# DM2097_Power_Supply.net
KiCad netlist of a schematic drawn in Altium Designer
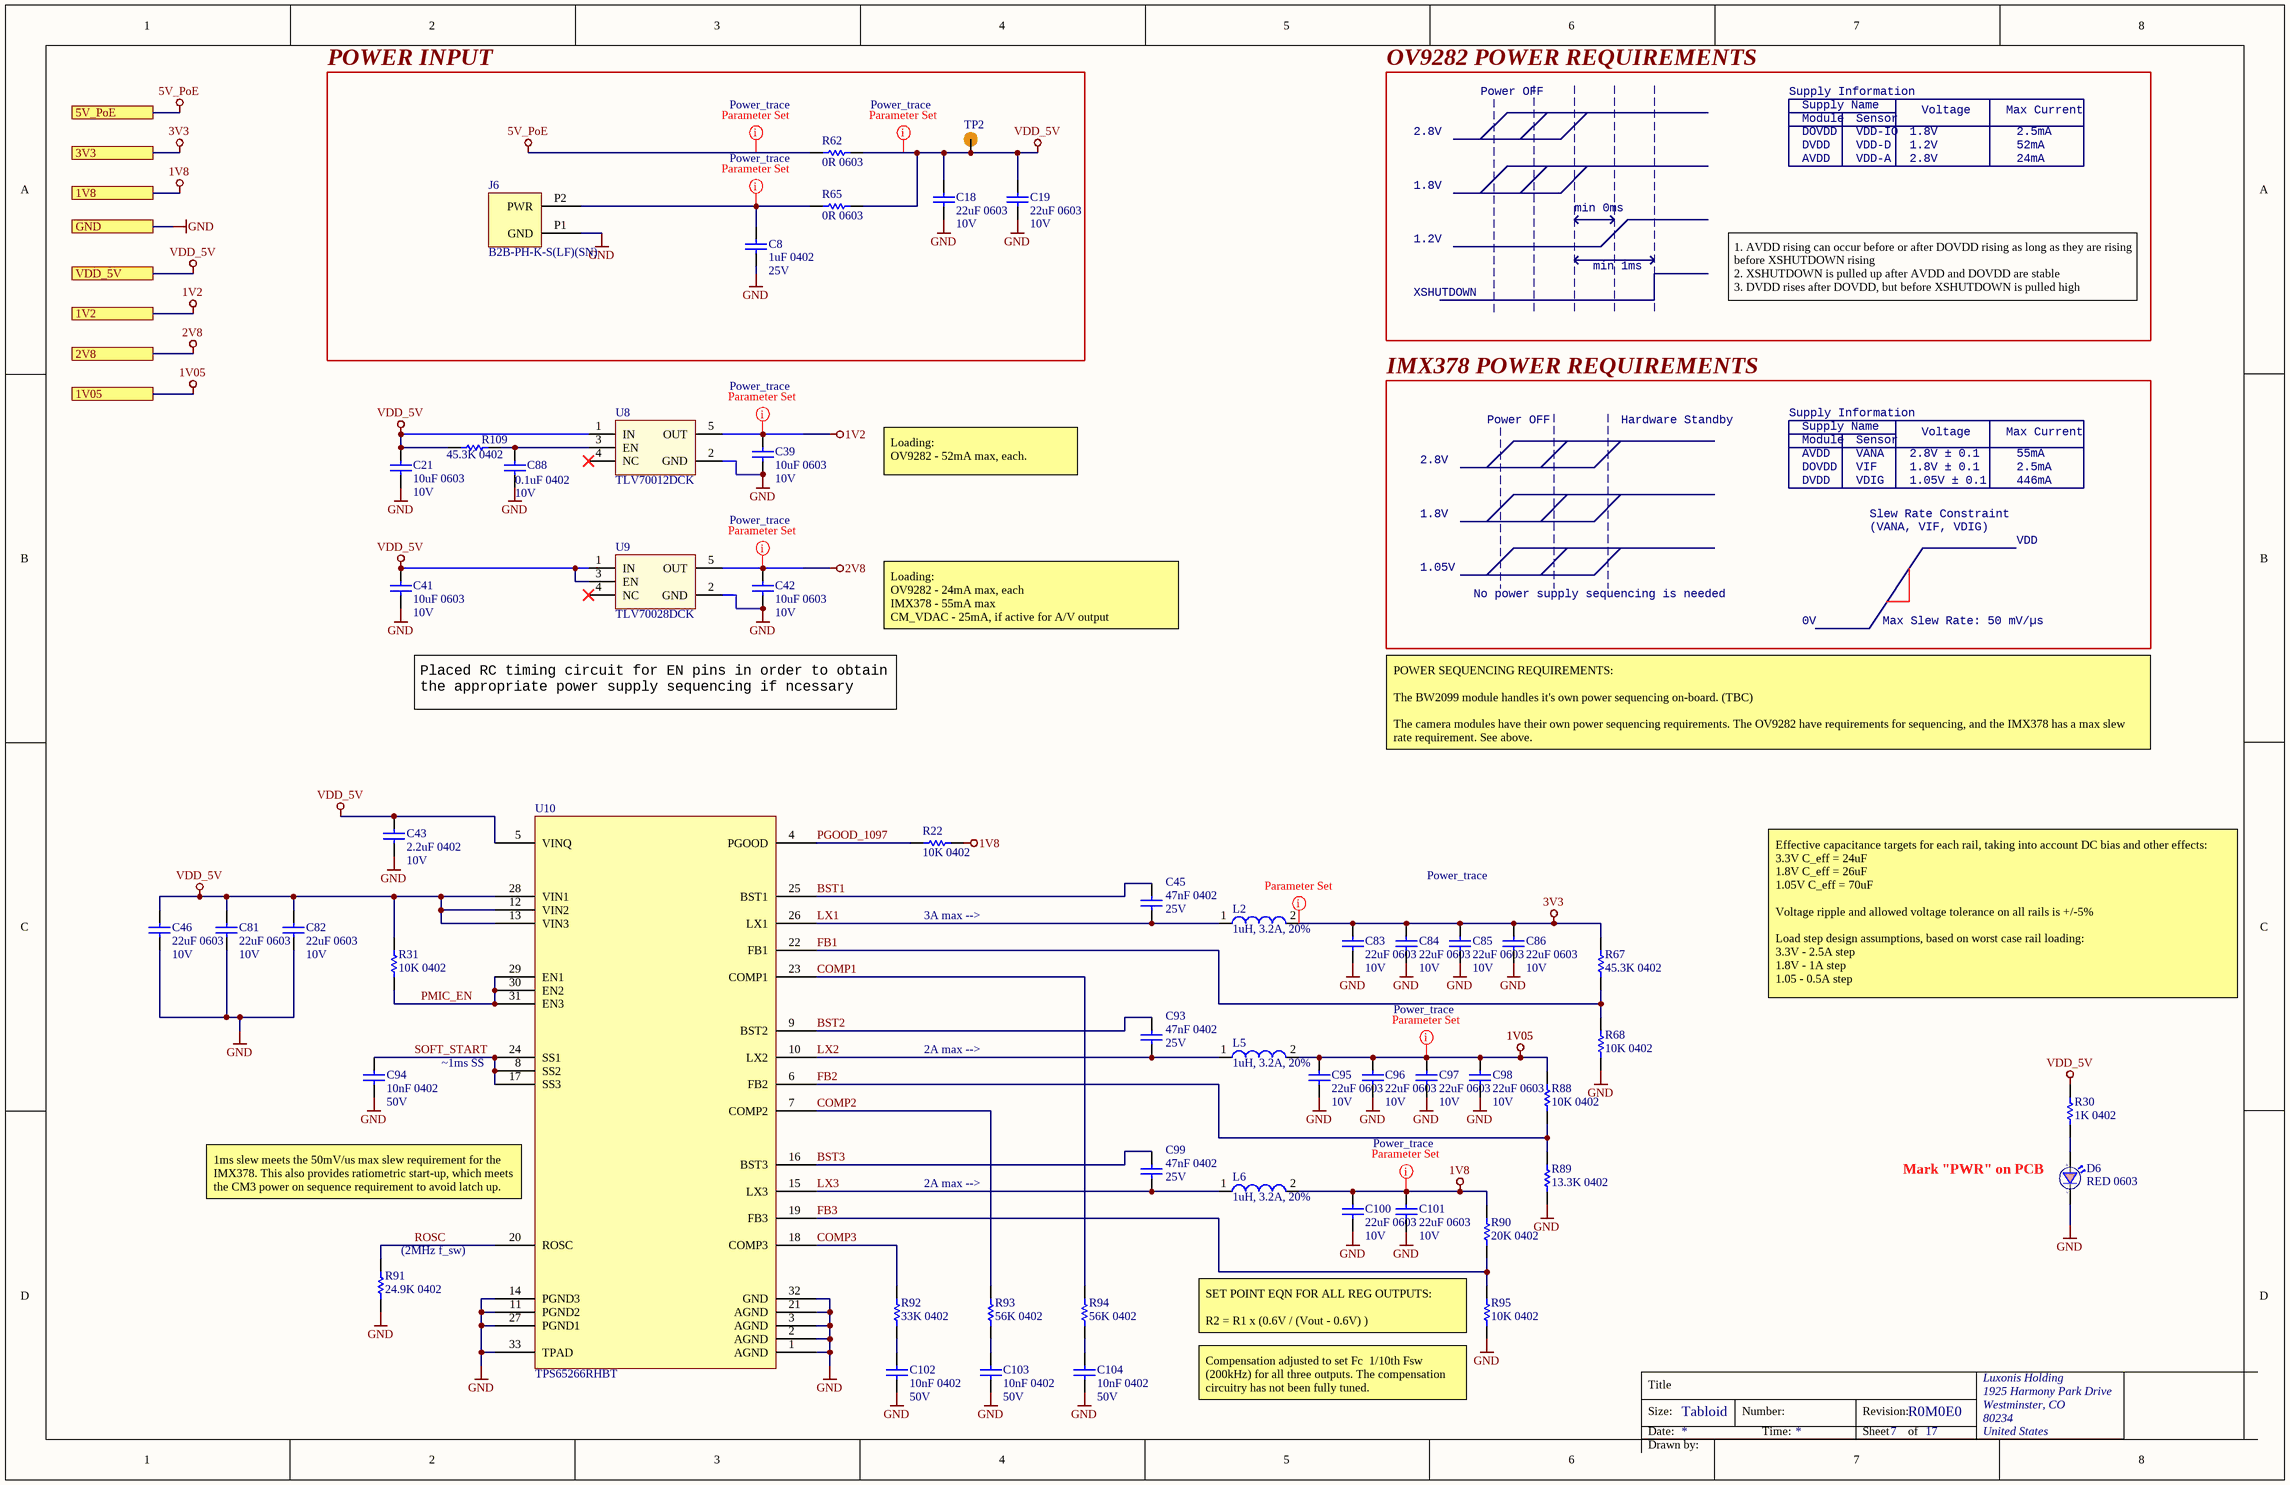
[diagram p0: DM2097_Power_Supply.SchDoc]

(export (version "E")
  (design (tool "Eeschema 10.0.6"))
  (components
    (comp (ref "C8")
      (value "1uF 0402")
      (footprint "CAP_Altium_Vault_Generic:CAPC0402(1005)70_L")
      (description "CAP CER 1UF 25V X5R 0402 10%")
      (fields
        (field (name "TOLERANCE") "10%")
        (field (name "VOLTAGE") "25V")
        (field (name "VOLTAGE RATING") "25V")
      )
      (libsource (lib "LuxonisMaster") (part "GRM155R61E105KA12D"))
    )
    (comp (ref "C18")
      (value "22uF 0603")
      (footprint "CAP_Altium_Vault_Generic:CAPC0603(1608)100_L")
      (description "CAP CER 22UF 10V X5R 0603 20%")
      (fields (field (name "TOLERANCE") "20%") (field (name "VOLTAGE RATING") "10V"))
      (libsource (lib "LuxonisMaster") (part "GRM188R61A226ME15D"))
    )
    (comp (ref "C19")
      (value "22uF 0603")
      (footprint "CAP_Altium_Vault_Generic:CAPC0603(1608)100_L")
      (description "CAP CER 22UF 10V X5R 0603 20%")
      (fields (field (name "TOLERANCE") "20%") (field (name "VOLTAGE RATING") "10V"))
      (libsource (lib "LuxonisMaster") (part "GRM188R61A226ME15D"))
    )
    (comp (ref "C21")
      (value "10uF 0603")
      (footprint "CAP_Altium_Vault_Generic:CAPC0603(1608)100_N")
      (description "CAP CER 10UF 10V X5R 0603 20%")
      (fields (field (name "TOLERANCE") "20%") (field (name "VOLTAGE RATING") "10V"))
      (libsource (lib "LuxonisMaster") (part "GRM188R61A106ME69D"))
    )
    (comp (ref "C39")
      (value "10uF 0603")
      (footprint "CAP_Altium_Vault_Generic:CAPC0603(1608)100_N")
      (description "CAP CER 10UF 10V X5R 0603 20%")
      (fields (field (name "TOLERANCE") "20%") (field (name "VOLTAGE RATING") "10V"))
      (libsource (lib "LuxonisMaster") (part "GRM188R61A106ME69D"))
    )
    (comp (ref "C41")
      (value "10uF 0603")
      (footprint "CAP_Altium_Vault_Generic:CAPC0603(1608)100_N")
      (description "CAP CER 10UF 10V X5R 0603 20%")
      (fields (field (name "TOLERANCE") "20%") (field (name "VOLTAGE RATING") "10V"))
      (libsource (lib "LuxonisMaster") (part "GRM188R61A106ME69D"))
    )
    (comp (ref "C42")
      (value "10uF 0603")
      (footprint "CAP_Altium_Vault_Generic:CAPC0603(1608)100_N")
      (description "CAP CER 10UF 10V X5R 0603 20%")
      (fields (field (name "TOLERANCE") "20%") (field (name "VOLTAGE RATING") "10V"))
      (libsource (lib "LuxonisMaster") (part "GRM188R61A106ME69D"))
    )
    (comp (ref "C43")
      (value "2.2uF 0402")
      (footprint "CAP_Altium_Vault_Generic:CAPC0402(1005)70_N")
      (description "CAP CER 2.2UF 10V X5R 0402 10%")
      (fields (field (name "TOLERANCE") "10%") (field (name "VOLTAGE RATING") "10V"))
      (libsource (lib "LuxonisMaster") (part "GRM155R61A225KE95D"))
    )
    (comp (ref "C45")
      (value "47nF 0402")
      (footprint "CAP_Altium_Vault_Generic:CAPC0402(1005)70_N")
      (description "CAP CER 0.047UF 25V X7R 0402 10%")
      (fields
        (field (name "MANUFACTURER") "Murata")
        (field (name "MANUFACTURER PART NUMBER") "GRM155R71E473KA88D")
        (field (name "VOLTAGE") "25V")
      )
      (libsource (lib "LuxonisMaster") (part "GRM155R71E473KA88D"))
    )
    (comp (ref "C46")
      (value "22uF 0603")
      (footprint "CAP_Altium_Vault_Generic:CAPC0603(1608)100_N")
      (description "CAP CER 22UF 10V X5R 0603 20%")
      (fields (field (name "TOLERANCE") "20%") (field (name "VOLTAGE RATING") "10V"))
      (libsource (lib "LuxonisMaster") (part "GRM188R61A226ME15D"))
    )
    (comp (ref "C81")
      (value "22uF 0603")
      (footprint "CAP_Altium_Vault_Generic:CAPC0603(1608)100_N")
      (description "CAP CER 22UF 10V X5R 0603 20%")
      (fields (field (name "TOLERANCE") "20%") (field (name "VOLTAGE RATING") "10V"))
      (libsource (lib "LuxonisMaster") (part "GRM188R61A226ME15D"))
    )
    (comp (ref "C82")
      (value "22uF 0603")
      (footprint "CAP_Altium_Vault_Generic:CAPC0603(1608)100_N")
      (description "CAP CER 22UF 10V X5R 0603 20%")
      (fields (field (name "TOLERANCE") "20%") (field (name "VOLTAGE RATING") "10V"))
      (libsource (lib "LuxonisMaster") (part "GRM188R61A226ME15D"))
    )
    (comp (ref "C83")
      (value "22uF 0603")
      (footprint "CAP_Altium_Vault_Generic:CAPC0603(1608)100_N")
      (description "CAP CER 22UF 10V X5R 0603 20%")
      (fields (field (name "TOLERANCE") "20%") (field (name "VOLTAGE RATING") "10V"))
      (libsource (lib "LuxonisMaster") (part "GRM188R61A226ME15D"))
    )
    (comp (ref "C84")
      (value "22uF 0603")
      (footprint "CAP_Altium_Vault_Generic:CAPC0603(1608)100_N")
      (description "CAP CER 22UF 10V X5R 0603 20%")
      (fields (field (name "TOLERANCE") "20%") (field (name "VOLTAGE RATING") "10V"))
      (libsource (lib "LuxonisMaster") (part "GRM188R61A226ME15D"))
    )
    (comp (ref "C85")
      (value "22uF 0603")
      (footprint "CAP_Altium_Vault_Generic:CAPC0603(1608)100_N")
      (description "CAP CER 22UF 10V X5R 0603 20%")
      (fields (field (name "TOLERANCE") "20%") (field (name "VOLTAGE RATING") "10V"))
      (libsource (lib "LuxonisMaster") (part "GRM188R61A226ME15D"))
    )
    (comp (ref "C86")
      (value "22uF 0603")
      (footprint "CAP_Altium_Vault_Generic:CAPC0603(1608)100_N")
      (description "CAP CER 22UF 10V X5R 0603 20%")
      (fields (field (name "TOLERANCE") "20%") (field (name "VOLTAGE RATING") "10V"))
      (libsource (lib "LuxonisMaster") (part "GRM188R61A226ME15D"))
    )
    (comp (ref "C88")
      (value "0.1uF 0402")
      (footprint "CAP_Altium_Vault_Generic:CAPC0402(1005)70_L")
      (description "CAP CER 0.1UF 10V X7R 0402 5%")
      (fields (field (name "TOLERANCE") "5%") (field (name "VOLTAGE RATING") "10V"))
      (libsource (lib "LuxonisMaster") (part "GRM155R71A104JA01D"))
    )
    (comp (ref "C93")
      (value "47nF 0402")
      (footprint "CAP_Altium_Vault_Generic:CAPC0402(1005)70_N")
      (description "CAP CER 0.047UF 25V X7R 0402 10%")
      (fields
        (field (name "MANUFACTURER") "Murata")
        (field (name "MANUFACTURER PART NUMBER") "GRM155R71E473KA88D")
        (field (name "VOLTAGE") "25V")
      )
      (libsource (lib "LuxonisMaster") (part "GRM155R71E473KA88D"))
    )
    (comp (ref "C94")
      (value "10nF 0402")
      (footprint "CAP_Altium_Vault_Generic:CAPC0402(1005)60_N")
      (description "CAP CER 10000PF 50V X7R 0402")
      (fields
        (field (name "TOLERANCE") "10%")
        (field (name "VOLTAGE") "25V")
        (field (name "VOLTAGE RATING") "50V")
      )
      (libsource (lib "LuxonisMaster") (part "GRM155R71H103KA88D"))
    )
    (comp (ref "C95")
      (value "22uF 0603")
      (footprint "CAP_Altium_Vault_Generic:CAPC0603(1608)100_N")
      (description "CAP CER 22UF 10V X5R 0603 20%")
      (fields (field (name "TOLERANCE") "20%") (field (name "VOLTAGE RATING") "10V"))
      (libsource (lib "LuxonisMaster") (part "GRM188R61A226ME15D"))
    )
    (comp (ref "C96")
      (value "22uF 0603")
      (footprint "CAP_Altium_Vault_Generic:CAPC0603(1608)100_N")
      (description "CAP CER 22UF 10V X5R 0603 20%")
      (fields (field (name "TOLERANCE") "20%") (field (name "VOLTAGE RATING") "10V"))
      (libsource (lib "LuxonisMaster") (part "GRM188R61A226ME15D"))
    )
    (comp (ref "C97")
      (value "22uF 0603")
      (footprint "CAP_Altium_Vault_Generic:CAPC0603(1608)100_N")
      (description "CAP CER 22UF 10V X5R 0603 20%")
      (fields (field (name "TOLERANCE") "20%") (field (name "VOLTAGE RATING") "10V"))
      (libsource (lib "LuxonisMaster") (part "GRM188R61A226ME15D"))
    )
    (comp (ref "C98")
      (value "22uF 0603")
      (footprint "CAP_Altium_Vault_Generic:CAPC0603(1608)100_N")
      (description "CAP CER 22UF 10V X5R 0603 20%")
      (fields (field (name "TOLERANCE") "20%") (field (name "VOLTAGE RATING") "10V"))
      (libsource (lib "LuxonisMaster") (part "GRM188R61A226ME15D"))
    )
    (comp (ref "C99")
      (value "47nF 0402")
      (footprint "CAP_Altium_Vault_Generic:CAPC0402(1005)70_N")
      (description "CAP CER 0.047UF 25V X7R 0402 10%")
      (fields
        (field (name "MANUFACTURER") "Murata")
        (field (name "MANUFACTURER PART NUMBER") "GRM155R71E473KA88D")
        (field (name "VOLTAGE") "25V")
      )
      (libsource (lib "LuxonisMaster") (part "GRM155R71E473KA88D"))
    )
    (comp (ref "C100")
      (value "22uF 0603")
      (footprint "CAP_Altium_Vault_Generic:CAPC0603(1608)100_N")
      (description "CAP CER 22UF 10V X5R 0603 20%")
      (fields (field (name "TOLERANCE") "20%") (field (name "VOLTAGE RATING") "10V"))
      (libsource (lib "LuxonisMaster") (part "GRM188R61A226ME15D"))
    )
    (comp (ref "C101")
      (value "22uF 0603")
      (footprint "CAP_Altium_Vault_Generic:CAPC0603(1608)100_N")
      (description "CAP CER 22UF 10V X5R 0603 20%")
      (fields (field (name "TOLERANCE") "20%") (field (name "VOLTAGE RATING") "10V"))
      (libsource (lib "LuxonisMaster") (part "GRM188R61A226ME15D"))
    )
    (comp (ref "C102")
      (value "10nF 0402")
      (footprint "CAP_Altium_Vault_Generic:CAPC0402(1005)60_N")
      (description "CAP CER 10000PF 50V X7R 0402")
      (fields
        (field (name "TOLERANCE") "10%")
        (field (name "VOLTAGE") "25V")
        (field (name "VOLTAGE RATING") "50V")
      )
      (libsource (lib "LuxonisMaster") (part "GRM155R71H103KA88D"))
    )
    (comp (ref "C103")
      (value "10nF 0402")
      (footprint "CAP_Altium_Vault_Generic:CAPC0402(1005)60_N")
      (description "CAP CER 10000PF 50V X7R 0402")
      (fields
        (field (name "TOLERANCE") "10%")
        (field (name "VOLTAGE") "25V")
        (field (name "VOLTAGE RATING") "50V")
      )
      (libsource (lib "LuxonisMaster") (part "GRM155R71H103KA88D"))
    )
    (comp (ref "C104")
      (value "10nF 0402")
      (footprint "CAP_Altium_Vault_Generic:CAPC0402(1005)60_N")
      (description "CAP CER 10000PF 50V X7R 0402")
      (fields
        (field (name "TOLERANCE") "10%")
        (field (name "VOLTAGE") "25V")
        (field (name "VOLTAGE RATING") "50V")
      )
      (libsource (lib "LuxonisMaster") (part "GRM155R71H103KA88D"))
    )
    (comp (ref "D6")
      (value "RED 0603")
      (footprint "LuxonisMaster:SML_D1xx8W")
      (description "LED RED DIFFUSED 0603 SMD Red 620nm LED Indication - Discrete 2.2V 0603 (1608 Metric)")
      (libsource (lib "LuxonisMaster") (part "SML-D12U8WT86"))
    )
    (comp (ref "J6")
      (value "B2B-PH-K-S(LF)(SN)")
      (footprint "LuxonisMaster:B2B-PH-K-S(LF)(SN)")
      (description "CONN HEADER VERT 2POS 2MM")
      (libsource (lib "LuxonisMaster") (part "B2B-PH-K-S(LF)(SN)"))
    )
    (comp (ref "L2")
      (value "1uH, 3.2A, 20%")
      (footprint "LuxonisMaster:DFE252012P-1R0M=P2")
      (description "FIXED IND 1UH 3.2A 42 MOHM SMD")
      (fields
        (field (name "MANUFACTURER") "Murata")
        (field (name "MANUFACTURER PART NUMBER") "DFE252012P-1R0M=P2")
      )
      (libsource (lib "LuxonisMaster") (part "DFE252012P-1R0M=P2"))
    )
    (comp (ref "L5")
      (value "1uH, 3.2A, 20%")
      (footprint "LuxonisMaster:DFE252012P-1R0M=P2")
      (description "FIXED IND 1UH 3.2A 42 MOHM SMD")
      (fields
        (field (name "MANUFACTURER") "Murata")
        (field (name "MANUFACTURER PART NUMBER") "DFE252012P-1R0M=P2")
      )
      (libsource (lib "LuxonisMaster") (part "DFE252012P-1R0M=P2"))
    )
    (comp (ref "L6")
      (value "1uH, 3.2A, 20%")
      (footprint "LuxonisMaster:DFE252012P-1R0M=P2")
      (description "FIXED IND 1UH 3.2A 42 MOHM SMD")
      (fields
        (field (name "MANUFACTURER") "Murata")
        (field (name "MANUFACTURER PART NUMBER") "DFE252012P-1R0M=P2")
      )
      (libsource (lib "LuxonisMaster") (part "DFE252012P-1R0M=P2"))
    )
    (comp (ref "R22")
      (value "10K 0402")
      (footprint "RES_Altium_Vault_Generic:RESC0402(1005)_N")
      (fields (field (name "TOLERANCE") "1%"))
      (libsource (lib "LuxonisMaster") (part "RC0402FR-1310KL"))
    )
    (comp (ref "R30")
      (value "1K 0402")
      (footprint "RES_Altium_Vault_Generic:RESC0402(1005)_N")
      (fields (field (name "TOLERANCE") "1%"))
      (libsource (lib "LuxonisMaster") (part "RC0402FR-071KL"))
    )
    (comp (ref "R31")
      (value "10K 0402")
      (footprint "RES_Altium_Vault_Generic:RESC0402(1005)_N")
      (fields (field (name "TOLERANCE") "1%"))
      (libsource (lib "LuxonisMaster") (part "RC0402FR-1310KL"))
    )
    (comp (ref "R62")
      (value "0R 0603")
      (footprint "RES_Altium_Vault_Generic:RESC0603(1608)_N")
      (fields (field (name "TOLERANCE") "5%"))
      (libsource (lib "LuxonisMaster") (part "CRCW06030000Z0EA"))
    )
    (comp (ref "R65")
      (value "0R 0603")
      (footprint "RES_Altium_Vault_Generic:RESC0603(1608)_N")
      (fields (field (name "TOLERANCE") "5%"))
      (libsource (lib "LuxonisMaster") (part "CRCW06030000Z0EA"))
    )
    (comp (ref "R67")
      (value "45.3K 0402")
      (footprint "RES_Altium_Vault_Generic:RESC0402(1005)_N")
      (description "RES SMD 45.3K OHM 1% 1/16W 0402")
      (fields (field (name "TOLERANCE") "1%"))
      (libsource (lib "LuxonisMaster") (part "RC0402FR-0745K3L"))
    )
    (comp (ref "R68")
      (value "10K 0402")
      (footprint "RES_Altium_Vault_Generic:RESC0402(1005)_N")
      (fields (field (name "TOLERANCE") "1%"))
      (libsource (lib "LuxonisMaster") (part "RC0402FR-1310KL"))
    )
    (comp (ref "R88")
      (value "10K 0402")
      (footprint "RES_Altium_Vault_Generic:RESC0402(1005)_N")
      (fields (field (name "TOLERANCE") "1%"))
      (libsource (lib "LuxonisMaster") (part "RC0402FR-1310KL"))
    )
    (comp (ref "R89")
      (value "13.3K 0402")
      (footprint "RES_Altium_Vault_Generic:RESC0402(1005)_N")
      (description "RES SMD 13.3K OHM 1% 1/16W 0402")
      (fields (field (name "TOLERANCE") "1%"))
      (libsource (lib "LuxonisMaster") (part "RC0402FR-0713K3L"))
    )
    (comp (ref "R90")
      (value "20K 0402")
      (footprint "RES_Altium_Vault_Generic:RESC0402(1005)_N")
      (fields
        (field (name "MANUFACTURER") "Yageo")
        (field (name "MANUFACTURER PART NUMBER") "RC0402FR-0720KL")
        (field (name "TOLERANCE") "1%")
      )
      (libsource (lib "LuxonisMaster") (part "RC0402FR-0720KL"))
    )
    (comp (ref "R91")
      (value "24.9K 0402")
      (footprint "RES_Altium_Vault_Generic:RESC0402(1005)_N")
      (description "RES SMD 24.9K OHM 1% 1/16W 0402")
      (fields (field (name "TOLERANCE") "1%"))
      (libsource (lib "LuxonisMaster") (part "RC0402FR-0724K9L"))
    )
    (comp (ref "R92")
      (value "33K 0402")
      (footprint "RES_Altium_Vault_Generic:RESC0402(1005)_N")
      (description "RES SMD 33K OHM 1% 1/16W 0402")
      (fields (field (name "TOLERANCE") "1%"))
      (libsource (lib "LuxonisMaster") (part "CRCW040233K0FKED"))
    )
    (comp (ref "R93")
      (value "56K 0402")
      (footprint "RES_Altium_Vault_Generic:RESC0402(1005)_N")
      (fields
        (field (name "MANUFACTURER") "Yageo")
        (field (name "MANUFACTURER PART NUMBER") "RC0402FR-0756KL")
        (field (name "TOLERANCE") "1%")
      )
      (libsource (lib "LuxonisMaster") (part "RC0402FR-0756KL"))
    )
    (comp (ref "R94")
      (value "56K 0402")
      (footprint "RES_Altium_Vault_Generic:RESC0402(1005)_N")
      (fields
        (field (name "MANUFACTURER") "Yageo")
        (field (name "MANUFACTURER PART NUMBER") "RC0402FR-0756KL")
        (field (name "TOLERANCE") "1%")
      )
      (libsource (lib "LuxonisMaster") (part "RC0402FR-0756KL"))
    )
    (comp (ref "R95")
      (value "10K 0402")
      (footprint "RES_Altium_Vault_Generic:RESC0402(1005)_N")
      (fields (field (name "TOLERANCE") "1%"))
      (libsource (lib "LuxonisMaster") (part "RC0402FR-1310KL"))
    )
    (comp (ref "R109")
      (value "45.3K 0402")
      (footprint "RES_Altium_Vault_Generic:RESC0402(1005)_L")
      (description "RES SMD 45.3K OHM 1% 1/16W 0402")
      (fields (field (name "TOLERANCE") "1%"))
      (libsource (lib "LuxonisMaster") (part "RC0402FR-0745K3L"))
    )
    (comp (ref "TP2")
      (value "TP100_200_NS")
      (footprint "LuxonisMaster:TP100_200_NS")
      (libsource (lib "LuxonisMaster") (part "TEST_POINT"))
    )
    (comp (ref "U8")
      (value "TLV70012DCK")
      (footprint "LuxonisMaster:TLV70012DCK")
      (description "IC REG LINEAR 1.2V 200MA SC70-5")
      (libsource (lib "LuxonisMaster") (part "TLV70012DCK"))
    )
    (comp (ref "U9")
      (value "TLV70028DCK")
      (footprint "LuxonisMaster:TLV70028DCK")
      (description "IC REG LINEAR 2.8V 200MA SC70-5 Linear Voltage Regulator IC  1 Output  200mA SC-70-5")
      (libsource (lib "LuxonisMaster") (part "TLV70028DCK"))
    )
    (comp (ref "U10")
      (value "TPS65266RHBT")
      (footprint "LuxonisMaster:TPS65266RHBT")
      (description "2.7V to 6.5V Input, 3A/2A/2A Triple Buck Converter 32-VQFN -40 to 85")
      (libsource (lib "LuxonisMaster") (part "TPS65266RHBT"))
    )
  )
  (nets
    (net (code "1") (name "/BST1") (class "Default")
      (node (ref "C45") (pin "1") (pinfunction "1_1") (pintype "passive"))
      (node (ref "U10") (pin "25") (pinfunction "BST1_25") (pintype "passive"))
    )
    (net (code "2") (name "/BST2") (class "Default")
      (node (ref "C93") (pin "1") (pinfunction "1_1") (pintype "passive"))
      (node (ref "U10") (pin "9") (pinfunction "BST2_9") (pintype "passive"))
    )
    (net (code "3") (name "/BST3") (class "Default")
      (node (ref "C99") (pin "1") (pinfunction "1_1") (pintype "passive"))
      (node (ref "U10") (pin "16") (pinfunction "BST3_16") (pintype "passive"))
    )
    (net (code "4") (name "/COMP1") (class "Default")
      (node (ref "R94") (pin "2") (pinfunction "2_2") (pintype "passive"))
      (node (ref "U10") (pin "23") (pinfunction "COMP1_23") (pintype "passive"))
    )
    (net (code "5") (name "/COMP2") (class "Default")
      (node (ref "R93") (pin "2") (pinfunction "2_2") (pintype "passive"))
      (node (ref "U10") (pin "7") (pinfunction "COMP2_7") (pintype "passive"))
    )
    (net (code "6") (name "/COMP3") (class "Default")
      (node (ref "R92") (pin "2") (pinfunction "2_2") (pintype "passive"))
      (node (ref "U10") (pin "18") (pinfunction "COMP3_18") (pintype "passive"))
    )
    (net (code "7") (name "/FB1") (class "Default")
      (node (ref "R67") (pin "1") (pinfunction "1_1") (pintype "passive"))
      (node (ref "R68") (pin "2") (pinfunction "2_2") (pintype "passive"))
      (node (ref "U10") (pin "22") (pinfunction "FB1_22") (pintype "passive"))
    )
    (net (code "8") (name "/FB2") (class "Default")
      (node (ref "R88") (pin "1") (pinfunction "1_1") (pintype "passive"))
      (node (ref "R89") (pin "2") (pinfunction "2_2") (pintype "passive"))
      (node (ref "U10") (pin "6") (pinfunction "FB2_6") (pintype "passive"))
    )
    (net (code "9") (name "/FB3") (class "Default")
      (node (ref "R90") (pin "1") (pinfunction "1_1") (pintype "passive"))
      (node (ref "R95") (pin "2") (pinfunction "2_2") (pintype "passive"))
      (node (ref "U10") (pin "19") (pinfunction "FB3_19") (pintype "passive"))
    )
    (net (code "10") (name "/LX1") (class "Default")
      (node (ref "C45") (pin "2") (pinfunction "2_2") (pintype "passive"))
      (node (ref "L2") (pin "1") (pinfunction "1_1") (pintype "passive"))
      (node (ref "U10") (pin "26") (pinfunction "LX1_26") (pintype "passive"))
    )
    (net (code "11") (name "/LX2") (class "Default")
      (node (ref "C93") (pin "2") (pinfunction "2_2") (pintype "passive"))
      (node (ref "L5") (pin "1") (pinfunction "1_1") (pintype "passive"))
      (node (ref "U10") (pin "10") (pinfunction "LX2_10") (pintype "passive"))
    )
    (net (code "12") (name "/LX3") (class "Default")
      (node (ref "C99") (pin "2") (pinfunction "2_2") (pintype "passive"))
      (node (ref "L6") (pin "1") (pinfunction "1_1") (pintype "passive"))
      (node (ref "U10") (pin "15") (pinfunction "LX3_15") (pintype "passive"))
    )
    (net (code "13") (name "/PGOOD_1097") (class "Default")
      (node (ref "R22") (pin "1") (pinfunction "1_1") (pintype "passive"))
      (node (ref "U10") (pin "4") (pinfunction "PGOOD_4") (pintype "passive"))
    )
    (net (code "14") (name "/PMIC_EN") (class "Default")
      (node (ref "R31") (pin "1") (pinfunction "1_1") (pintype "passive"))
      (node (ref "U10") (pin "29") (pinfunction "EN1_29") (pintype "passive"))
      (node (ref "U10") (pin "30") (pinfunction "EN2_30") (pintype "passive"))
      (node (ref "U10") (pin "31") (pinfunction "EN3_31") (pintype "passive"))
    )
    (net (code "15") (name "/ROSC") (class "Default")
      (node (ref "R91") (pin "2") (pinfunction "2_2") (pintype "passive"))
      (node (ref "U10") (pin "20") (pinfunction "ROSC_20") (pintype "passive"))
    )
    (net (code "16") (name "/SOFT_START") (class "Default")
      (node (ref "C94") (pin "1") (pinfunction "1_1") (pintype "passive"))
      (node (ref "U10") (pin "17") (pinfunction "SS3_17") (pintype "passive"))
      (node (ref "U10") (pin "24") (pinfunction "SS1_24") (pintype "passive"))
      (node (ref "U10") (pin "8") (pinfunction "SS2_8") (pintype "passive"))
    )
    (net (code "17") (name "1V2") (class "Default")
      (node (ref "C39") (pin "2") (pinfunction "2_2") (pintype "passive"))
      (node (ref "U8") (pin "5") (pinfunction "OUT_5") (pintype "passive"))
    )
    (net (code "18") (name "1V05") (class "Default")
      (node (ref "C95") (pin "1") (pinfunction "1_1") (pintype "passive"))
      (node (ref "C96") (pin "1") (pinfunction "1_1") (pintype "passive"))
      (node (ref "C97") (pin "1") (pinfunction "1_1") (pintype "passive"))
      (node (ref "C98") (pin "1") (pinfunction "1_1") (pintype "passive"))
      (node (ref "L5") (pin "2") (pinfunction "2_2") (pintype "passive"))
      (node (ref "R88") (pin "2") (pinfunction "2_2") (pintype "passive"))
    )
    (net (code "19") (name "1V8") (class "Default")
      (node (ref "C100") (pin "1") (pinfunction "1_1") (pintype "passive"))
      (node (ref "C101") (pin "1") (pinfunction "1_1") (pintype "passive"))
      (node (ref "L6") (pin "2") (pinfunction "2_2") (pintype "passive"))
      (node (ref "R22") (pin "2") (pinfunction "2_2") (pintype "passive"))
      (node (ref "R90") (pin "2") (pinfunction "2_2") (pintype "passive"))
    )
    (net (code "20") (name "2V8") (class "Default")
      (node (ref "C42") (pin "2") (pinfunction "2_2") (pintype "passive"))
      (node (ref "U9") (pin "5") (pinfunction "OUT_5") (pintype "passive"))
    )
    (net (code "21") (name "3V3") (class "Default")
      (node (ref "C83") (pin "1") (pinfunction "1_1") (pintype "passive"))
      (node (ref "C84") (pin "1") (pinfunction "1_1") (pintype "passive"))
      (node (ref "C85") (pin "1") (pinfunction "1_1") (pintype "passive"))
      (node (ref "C86") (pin "1") (pinfunction "1_1") (pintype "passive"))
      (node (ref "L2") (pin "2") (pinfunction "2_2") (pintype "passive"))
      (node (ref "R67") (pin "2") (pinfunction "2_2") (pintype "passive"))
    )
    (net (code "22") (name "5V_PoE") (class "Default")
      (node (ref "R62") (pin "1") (pinfunction "1_1") (pintype "passive"))
    )
    (net (code "23") (name "GND") (class "Default")
      (node (ref "C100") (pin "2") (pinfunction "2_2") (pintype "passive"))
      (node (ref "C101") (pin "2") (pinfunction "2_2") (pintype "passive"))
      (node (ref "C102") (pin "2") (pinfunction "2_2") (pintype "passive"))
      (node (ref "C103") (pin "2") (pinfunction "2_2") (pintype "passive"))
      (node (ref "C104") (pin "2") (pinfunction "2_2") (pintype "passive"))
      (node (ref "C18") (pin "1") (pinfunction "1_1") (pintype "passive"))
      (node (ref "C19") (pin "1") (pinfunction "1_1") (pintype "passive"))
      (node (ref "C21") (pin "1") (pinfunction "1_1") (pintype "passive"))
      (node (ref "C39") (pin "1") (pinfunction "1_1") (pintype "passive"))
      (node (ref "C41") (pin "1") (pinfunction "1_1") (pintype "passive"))
      (node (ref "C42") (pin "1") (pinfunction "1_1") (pintype "passive"))
      (node (ref "C43") (pin "2") (pinfunction "2_2") (pintype "passive"))
      (node (ref "C46") (pin "2") (pinfunction "2_2") (pintype "passive"))
      (node (ref "C8") (pin "1") (pinfunction "1_1") (pintype "passive"))
      (node (ref "C81") (pin "2") (pinfunction "2_2") (pintype "passive"))
      (node (ref "C82") (pin "2") (pinfunction "2_2") (pintype "passive"))
      (node (ref "C83") (pin "2") (pinfunction "2_2") (pintype "passive"))
      (node (ref "C84") (pin "2") (pinfunction "2_2") (pintype "passive"))
      (node (ref "C85") (pin "2") (pinfunction "2_2") (pintype "passive"))
      (node (ref "C86") (pin "2") (pinfunction "2_2") (pintype "passive"))
      (node (ref "C88") (pin "1") (pinfunction "1_1") (pintype "passive"))
      (node (ref "C94") (pin "2") (pinfunction "2_2") (pintype "passive"))
      (node (ref "C95") (pin "2") (pinfunction "2_2") (pintype "passive"))
      (node (ref "C96") (pin "2") (pinfunction "2_2") (pintype "passive"))
      (node (ref "C97") (pin "2") (pinfunction "2_2") (pintype "passive"))
      (node (ref "C98") (pin "2") (pinfunction "2_2") (pintype "passive"))
      (node (ref "D6") (pin "1") (pinfunction "C_1") (pintype "passive"))
      (node (ref "J6") (pin "P1") (pinfunction "GND_P1") (pintype "passive"))
      (node (ref "R68") (pin "1") (pinfunction "1_1") (pintype "passive"))
      (node (ref "R89") (pin "1") (pinfunction "1_1") (pintype "passive"))
      (node (ref "R91") (pin "1") (pinfunction "1_1") (pintype "passive"))
      (node (ref "R95") (pin "1") (pinfunction "1_1") (pintype "passive"))
      (node (ref "U10") (pin "1") (pinfunction "AGND_1") (pintype "passive"))
      (node (ref "U10") (pin "11") (pinfunction "PGND2_11") (pintype "passive"))
      (node (ref "U10") (pin "14") (pinfunction "PGND3_14") (pintype "passive"))
      (node (ref "U10") (pin "2") (pinfunction "AGND_2") (pintype "passive"))
      (node (ref "U10") (pin "21") (pinfunction "AGND_21") (pintype "passive"))
      (node (ref "U10") (pin "27") (pinfunction "PGND1_27") (pintype "passive"))
      (node (ref "U10") (pin "3") (pinfunction "AGND_3") (pintype "passive"))
      (node (ref "U10") (pin "32") (pinfunction "GND_32") (pintype "passive"))
      (node (ref "U10") (pin "33") (pinfunction "TPAD_33") (pintype "passive"))
      (node (ref "U8") (pin "2") (pinfunction "GND_2") (pintype "passive"))
      (node (ref "U9") (pin "2") (pinfunction "GND_2") (pintype "passive"))
    )
    (net (code "24") (name "Net-(C102-Pad1)") (class "Default")
      (node (ref "C102") (pin "1") (pinfunction "1_1") (pintype "passive"))
      (node (ref "R92") (pin "1") (pinfunction "1_1") (pintype "passive"))
    )
    (net (code "25") (name "Net-(C103-Pad1)") (class "Default")
      (node (ref "C103") (pin "1") (pinfunction "1_1") (pintype "passive"))
      (node (ref "R93") (pin "1") (pinfunction "1_1") (pintype "passive"))
    )
    (net (code "26") (name "Net-(C104-Pad1)") (class "Default")
      (node (ref "C104") (pin "1") (pinfunction "1_1") (pintype "passive"))
      (node (ref "R94") (pin "1") (pinfunction "1_1") (pintype "passive"))
    )
    (net (code "27") (name "Net-(D6-A)") (class "Default")
      (node (ref "D6") (pin "2") (pinfunction "A_2") (pintype "passive"))
      (node (ref "R30") (pin "1") (pinfunction "1_1") (pintype "passive"))
    )
    (net (code "28") (name "Net-(J6-PWR)") (class "Default")
      (node (ref "C8") (pin "2") (pinfunction "2_2") (pintype "passive"))
      (node (ref "J6") (pin "P2") (pinfunction "PWR_P2") (pintype "passive"))
      (node (ref "R65") (pin "1") (pinfunction "1_1") (pintype "passive"))
    )
    (net (code "29") (name "Net-(U8-EN)") (class "Default")
      (node (ref "C88") (pin "2") (pinfunction "2_2") (pintype "passive"))
      (node (ref "R109") (pin "1") (pinfunction "1_1") (pintype "passive"))
      (node (ref "U8") (pin "3") (pinfunction "EN_3") (pintype "passive"))
    )
    (net (code "30") (name "VDD_5V") (class "Default")
      (node (ref "C18") (pin "2") (pinfunction "2_2") (pintype "passive"))
      (node (ref "C19") (pin "2") (pinfunction "2_2") (pintype "passive"))
      (node (ref "C21") (pin "2") (pinfunction "2_2") (pintype "passive"))
      (node (ref "C41") (pin "2") (pinfunction "2_2") (pintype "passive"))
      (node (ref "C43") (pin "1") (pinfunction "1_1") (pintype "passive"))
      (node (ref "C46") (pin "1") (pinfunction "1_1") (pintype "passive"))
      (node (ref "C81") (pin "1") (pinfunction "1_1") (pintype "passive"))
      (node (ref "C82") (pin "1") (pinfunction "1_1") (pintype "passive"))
      (node (ref "R109") (pin "2") (pinfunction "2_2") (pintype "passive"))
      (node (ref "R30") (pin "2") (pinfunction "2_2") (pintype "passive"))
      (node (ref "R31") (pin "2") (pinfunction "2_2") (pintype "passive"))
      (node (ref "R62") (pin "2") (pinfunction "2_2") (pintype "passive"))
      (node (ref "R65") (pin "2") (pinfunction "2_2") (pintype "passive"))
      (node (ref "TP2") (pin "1") (pintype "passive"))
      (node (ref "U10") (pin "12") (pinfunction "VIN2_12") (pintype "passive"))
      (node (ref "U10") (pin "13") (pinfunction "VIN3_13") (pintype "passive"))
      (node (ref "U10") (pin "28") (pinfunction "VIN1_28") (pintype "passive"))
      (node (ref "U10") (pin "5") (pinfunction "VINQ_5") (pintype "passive"))
      (node (ref "U8") (pin "1") (pinfunction "IN_1") (pintype "passive"))
      (node (ref "U9") (pin "1") (pinfunction "IN_1") (pintype "passive"))
      (node (ref "U9") (pin "3") (pinfunction "EN_3") (pintype "passive"))
    )
    (net (code "31") (name "unconnected-(U8-NC-Pad4)") (class "Default")
      (node (ref "U8") (pin "4") (pinfunction "NC_4") (pintype "passive+no_connect"))
    )
    (net (code "32") (name "unconnected-(U9-NC-Pad4)") (class "Default")
      (node (ref "U9") (pin "4") (pinfunction "NC_4") (pintype "passive+no_connect"))
    )
  )
)
